# first_try.net
KiCad netlist of a schematic drawn in EAGLE
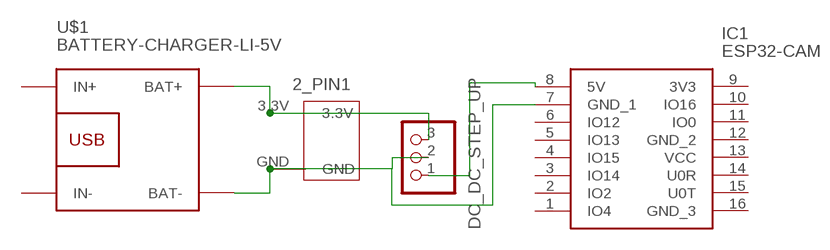
[diagram p0: schematic, sheet 1]

(export (version "E")
  (design (tool "Eeschema 10.0.6"))
  (components
    (comp (ref "2_PIN1")
      (value "2_PIN_HEADER")
      (footprint "eagle-import:2_PIN_HEADER")
      (libsource (lib "eagle-import") (part "2_PIN_HEADER"))
    )
    (comp (ref "DC_DC_STEP_UP")
      (value "PINHD-1X3")
      (footprint "eagle-import:1X03")
      (libsource (lib "eagle-import") (part "PINHD-1X3"))
    )
    (comp (ref "IC1")
      (value "ESP32-CAM")
      (footprint "eagle-import:ESP32CAM")
      (libsource (lib "eagle-import") (part "ESP32-CAM"))
    )
    (comp (ref "U$1")
      (value "BATTERY-CHARGER-LI-5V")
      (footprint "eagle-import:BATTERY-CHARGER-LI-5V")
      (libsource (lib "eagle-import") (part "BATTERY-CHARGER-LI-5V"))
    )
  )
  (nets
    (net (code "1") (name "Net-(2_PIN1-Pad3.3V)") (class "Default")
      (node (ref "2_PIN1") (pin "3.3V") (pinfunction "3.3V_3.3V") (pintype "bidirectional"))
      (node (ref "DC_DC_STEP_UP") (pin "3") (pinfunction "3_3") (pintype "passive"))
      (node (ref "U$1") (pin "BAT+") (pinfunction "BAT+_BAT+") (pintype "bidirectional"))
    )
    (net (code "2") (name "Net-(IC1-5V)") (class "Default")
      (node (ref "DC_DC_STEP_UP") (pin "1") (pinfunction "1_1") (pintype "passive"))
      (node (ref "IC1") (pin "8") (pinfunction "5V_8") (pintype "bidirectional"))
    )
    (net (code "3") (name "Net-(IC1-GND_1)") (class "Default")
      (node (ref "2_PIN1") (pin "GND") (pinfunction "GND_GND") (pintype "bidirectional"))
      (node (ref "DC_DC_STEP_UP") (pin "2") (pinfunction "2_2") (pintype "passive"))
      (node (ref "IC1") (pin "7") (pinfunction "GND_1_7") (pintype "bidirectional"))
      (node (ref "U$1") (pin "BAT-") (pinfunction "BAT-_BAT-") (pintype "bidirectional"))
    )
    (net (code "4") (name "unconnected-(IC1-3V3-Pad9)") (class "Default")
      (node (ref "IC1") (pin "9") (pinfunction "3V3_9") (pintype "bidirectional"))
    )
    (net (code "5") (name "unconnected-(IC1-GND_2-Pad12)") (class "Default")
      (node (ref "IC1") (pin "12") (pinfunction "GND_2_12") (pintype "bidirectional"))
    )
    (net (code "6") (name "unconnected-(IC1-GND_3-Pad16)") (class "Default")
      (node (ref "IC1") (pin "16") (pinfunction "GND_3_16") (pintype "bidirectional"))
    )
    (net (code "7") (name "unconnected-(IC1-IO0-Pad11)") (class "Default")
      (node (ref "IC1") (pin "11") (pinfunction "IO0_11") (pintype "bidirectional"))
    )
    (net (code "8") (name "unconnected-(IC1-IO2-Pad2)") (class "Default")
      (node (ref "IC1") (pin "2") (pinfunction "IO2_2") (pintype "bidirectional"))
    )
    (net (code "9") (name "unconnected-(IC1-IO4-Pad1)") (class "Default")
      (node (ref "IC1") (pin "1") (pinfunction "IO4_1") (pintype "bidirectional"))
    )
    (net (code "10") (name "unconnected-(IC1-IO12-Pad6)") (class "Default")
      (node (ref "IC1") (pin "6") (pinfunction "IO12_6") (pintype "bidirectional"))
    )
    (net (code "11") (name "unconnected-(IC1-IO13-Pad5)") (class "Default")
      (node (ref "IC1") (pin "5") (pinfunction "IO13_5") (pintype "bidirectional"))
    )
    (net (code "12") (name "unconnected-(IC1-IO14-Pad3)") (class "Default")
      (node (ref "IC1") (pin "3") (pinfunction "IO14_3") (pintype "bidirectional"))
    )
    (net (code "13") (name "unconnected-(IC1-IO15-Pad4)") (class "Default")
      (node (ref "IC1") (pin "4") (pinfunction "IO15_4") (pintype "bidirectional"))
    )
    (net (code "14") (name "unconnected-(IC1-IO16-Pad10)") (class "Default")
      (node (ref "IC1") (pin "10") (pinfunction "IO16_10") (pintype "bidirectional"))
    )
    (net (code "15") (name "unconnected-(IC1-U0R-Pad14)") (class "Default")
      (node (ref "IC1") (pin "14") (pinfunction "U0R_14") (pintype "bidirectional"))
    )
    (net (code "16") (name "unconnected-(IC1-U0T-Pad15)") (class "Default")
      (node (ref "IC1") (pin "15") (pinfunction "U0T_15") (pintype "bidirectional"))
    )
    (net (code "17") (name "unconnected-(IC1-VCC-Pad13)") (class "Default")
      (node (ref "IC1") (pin "13") (pinfunction "VCC_13") (pintype "bidirectional"))
    )
    (net (code "18") (name "unconnected-(U$1-PadIN+)") (class "Default")
      (node (ref "U$1") (pin "IN+") (pinfunction "IN+_IN+") (pintype "bidirectional"))
    )
    (net (code "19") (name "unconnected-(U$1-PadIN-)") (class "Default")
      (node (ref "U$1") (pin "IN-") (pinfunction "IN-_IN-") (pintype "bidirectional"))
    )
  )
)
